# Arduino_nano.net
KiCad netlist of a schematic drawn in Altium Designer
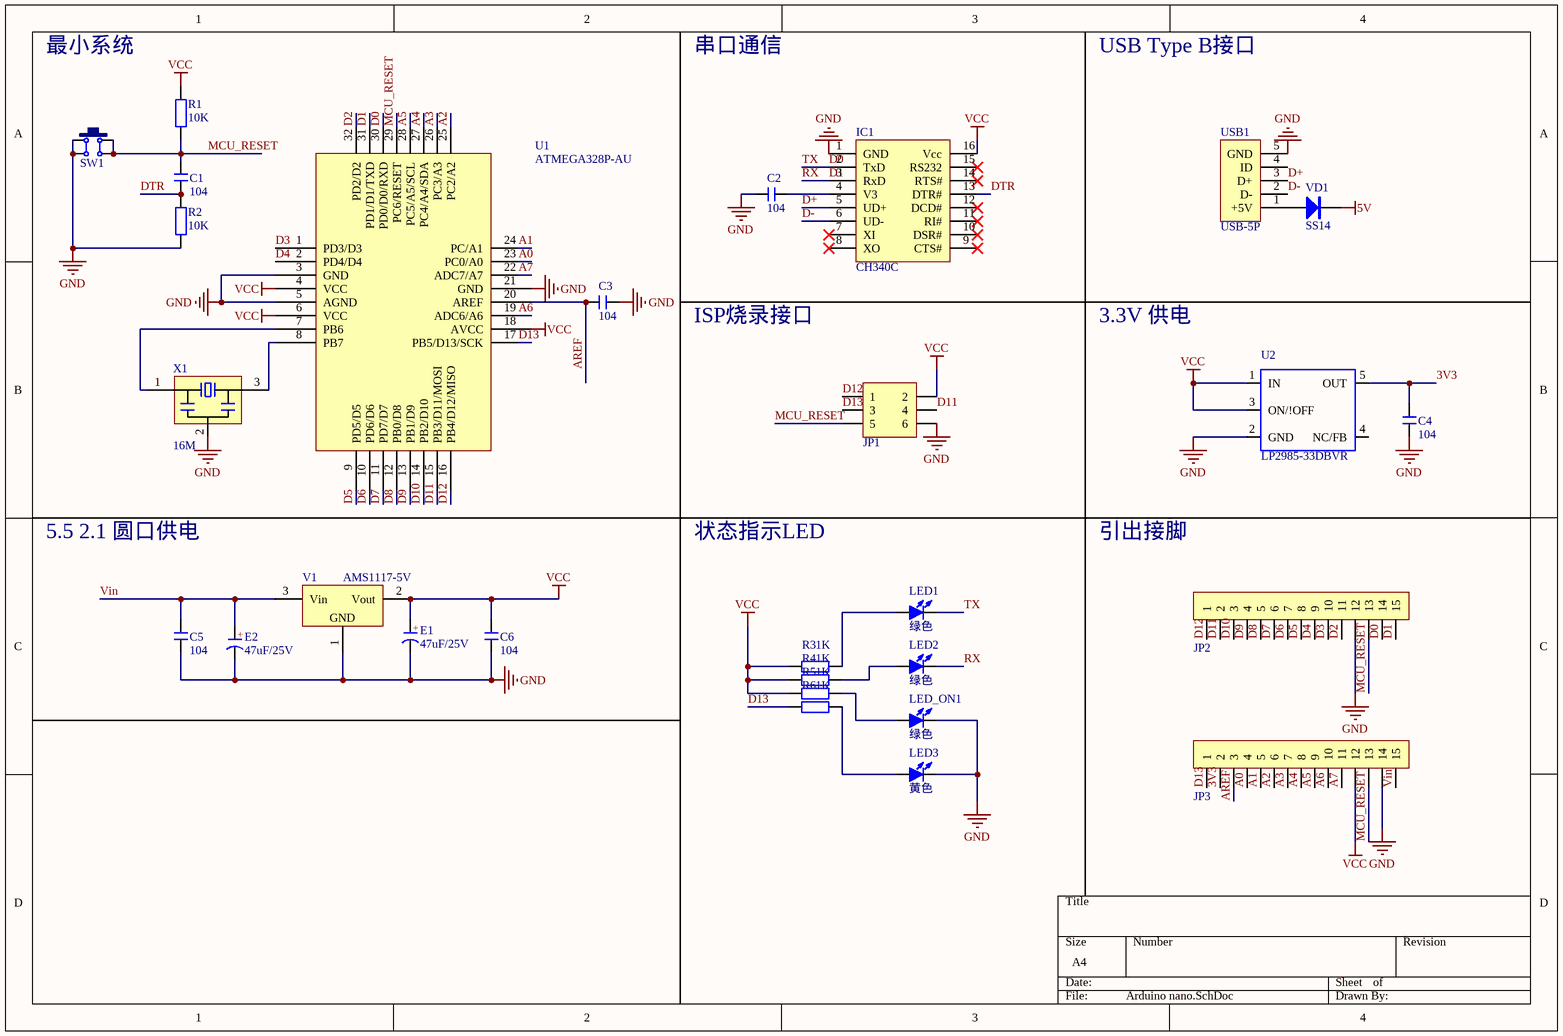
[diagram p0: Arduino nano.SchDoc]

(export (version "E")
  (design (tool "Eeschema 10.0.6"))
  (components
    (comp (ref "C1")
      (value "104")
      (footprint "C 0603_L")
      (description "无极性贴片电容")
      (fields (field (name "版权归属") "源创客"))
      (libsource (lib "电阻-电容-电感") (part "C"))
    )
    (comp (ref "C2")
      (value "104")
      (footprint "C 0603_L")
      (description "无极性贴片电容")
      (fields (field (name "版权归属") "源创客"))
      (libsource (lib "电阻-电容-电感") (part "C"))
    )
    (comp (ref "C3")
      (value "104")
      (footprint "C 0603_L")
      (description "无极性贴片电容")
      (fields (field (name "版权归属") "源创客"))
      (libsource (lib "电阻-电容-电感") (part "C"))
    )
    (comp (ref "C4")
      (value "104")
      (footprint "C 0603_L")
      (description "无极性贴片电容")
      (fields (field (name "版权归属") "源创客"))
      (libsource (lib "电阻-电容-电感") (part "C"))
    )
    (comp (ref "C5")
      (value "104")
      (footprint "C 0603_L")
      (description "无极性贴片电容")
      (fields (field (name "版权归属") "源创客"))
      (libsource (lib "电阻-电容-电感") (part "C"))
    )
    (comp (ref "C6")
      (value "104")
      (footprint "C 0603_L")
      (description "无极性贴片电容")
      (fields (field (name "版权归属") "源创客"))
      (libsource (lib "电阻-电容-电感") (part "C"))
    )
    (comp (ref "E1")
      (value "47uF/25V")
      (footprint "CD A(3216)")
      (description "贴片电解电容")
      (fields (field (name "版权归属") "源创客"))
      (libsource (lib "电阻-电容-电感") (part "C-CM"))
    )
    (comp (ref "E2")
      (value "47uF/25V")
      (footprint "CD A(3216)")
      (description "贴片电解电容")
      (fields (field (name "版权归属") "源创客"))
      (libsource (lib "电阻-电容-电感") (part "C-CM"))
    )
    (comp (ref "IC1")
      (value "CH340C")
      (footprint "SOP16_L")
      (description "串口转USB")
      (fields (field (name "版权归属") "源创客"))
      (libsource (lib "IC芯片") (part "CH340G"))
    )
    (comp (ref "JP1")
      (value "Header3X2")
      (footprint "HDR2.54-LI-2x3P")
      (description "3*2P接插件")
      (fields (field (name "版权归属") "源创客"))
      (libsource (lib "接插件") (part "Header 3X2"))
    )
    (comp (ref "JP2")
      (value "HDR-1X15")
      (footprint "HDR2.54-LI-15P")
      (description "15P接插件")
      (fields (field (name "版权归属") "源创客"))
      (libsource (lib "4.6   - 接插件-脚距2.54") (part "Header 15"))
    )
    (comp (ref "JP3")
      (value "HDR-1X15")
      (footprint "HDR2.54-LI-15P")
      (description "15P接插件")
      (fields (field (name "版权归属") "源创客"))
      (libsource (lib "4.6   - 接插件-脚距2.54") (part "Header 15"))
    )
    (comp (ref "LED1")
      (value "绿色")
      (footprint "LED 0603B")
      (description "贴片LED")
      (fields (field (name "版权归属") "源创客"))
      (libsource (lib "LED") (part "LED-SMD"))
    )
    (comp (ref "LED2")
      (value "绿色")
      (footprint "LED 0603B")
      (description "贴片LED")
      (fields (field (name "版权归属") "源创客"))
      (libsource (lib "LED") (part "LED-SMD"))
    )
    (comp (ref "LED3")
      (value "黄色")
      (footprint "LED 0603B")
      (description "贴片LED")
      (fields (field (name "版权归属") "源创客"))
      (libsource (lib "LED") (part "LED-SMD"))
    )
    (comp (ref "LED_ON1")
      (value "绿色")
      (footprint "LED 0603B")
      (description "贴片LED")
      (fields (field (name "版权归属") "源创客"))
      (libsource (lib "LED") (part "LED-SMD"))
    )
    (comp (ref "R1")
      (value "10K")
      (footprint "R 0603_L")
      (description "贴片电阻")
      (fields (field (name "版权归属") "源创客"))
      (libsource (lib "电阻-电容-电感") (part "R"))
    )
    (comp (ref "R2")
      (value "10K")
      (footprint "R 0603_L")
      (description "贴片电阻")
      (fields (field (name "版权归属") "源创客"))
      (libsource (lib "电阻-电容-电感") (part "R"))
    )
    (comp (ref "R3")
      (value "1K")
      (footprint "R 0603_L")
      (description "贴片电阻")
      (fields (field (name "版权归属") "源创客"))
      (libsource (lib "电阻-电容-电感") (part "R"))
    )
    (comp (ref "R4")
      (value "1K")
      (footprint "R 0603_L")
      (description "贴片电阻")
      (fields (field (name "版权归属") "源创客"))
      (libsource (lib "电阻-电容-电感") (part "R"))
    )
    (comp (ref "R5")
      (value "1K")
      (footprint "R 0603_L")
      (description "贴片电阻")
      (fields (field (name "版权归属") "源创客"))
      (libsource (lib "电阻-电容-电感") (part "R"))
    )
    (comp (ref "R6")
      (value "1K")
      (footprint "R 0603_L")
      (description "贴片电阻")
      (fields (field (name "版权归属") "源创客"))
      (libsource (lib "电阻-电容-电感") (part "R"))
    )
    (comp (ref "SW1")
      (value "4x4x1.5")
      (footprint "TS4x4x1.5")
      (description "防水轻触开关")
      (fields (field (name "版权归属") "源创客"))
      (libsource (lib "5.1   - 按键-开关") (part "TS-030"))
    )
    (comp (ref "U1")
      (value "ATMEGA328P-AU")
      (footprint "LQFP32 7X7_L")
      (description "AVR单片机")
      (fields (field (name "版权归属") "源创客"))
      (libsource (lib "Atmel系列单片机") (part "ATMEGA328P"))
    )
    (comp (ref "U2")
      (value "LP2985-33DBVR")
      (footprint "SOT23-5L")
      (libsource (lib "*") (part "LP2985-XXDBVR33"))
    )
    (comp (ref "USB1")
      (value "USB-5P")
      (footprint "USB-MICRO_A")
      (description "微型USB母座")
      (fields (field (name "版权归属") "源创客"))
      (libsource (lib "4.1   - 接口类") (part "USB-5P"))
    )
    (comp (ref "V1")
      (value "AMS1117-5V")
      (footprint "SOT223_N")
      (description "三端稳压芯片")
      (fields (field (name "版权归属") "源创客"))
      (libsource (lib "IC芯片") (part "AMS1117"))
    )
    (comp (ref "VD1")
      (value "SS14")
      (footprint "SMA")
      (description "肖特基二极管")
      (fields (field (name "版权归属") "源创客"))
      (libsource (lib "二极管-整流桥") (part "SS14"))
    )
    (comp (ref "X1")
      (value "16M")
      (footprint "OSC-3.2-1.3-3P")
      (description "3脚晶振")
      (fields (field (name "版权归属") "源创客"))
      (libsource (lib "保险丝-晶振") (part "XTAL-3"))
    )
  )
  (nets
    (net (code "1") (name "/3V3") (class "Default")
      (node (ref "C4") (pin "2") (pinfunction "2_2") (pintype "passive"))
      (node (ref "JP3") (pin "2") (pinfunction "2_2") (pintype "passive"))
      (node (ref "U2") (pin "5") (pinfunction "OUT_5") (pintype "passive"))
    )
    (net (code "2") (name "/A0") (class "Default")
      (node (ref "JP3") (pin "4") (pinfunction "4_4") (pintype "passive"))
      (node (ref "U1") (pin "23") (pinfunction "PC0/A0_23") (pintype "passive"))
    )
    (net (code "3") (name "/A1") (class "Default")
      (node (ref "JP3") (pin "5") (pinfunction "5_5") (pintype "passive"))
      (node (ref "U1") (pin "24") (pinfunction "PC/A1_24") (pintype "passive"))
    )
    (net (code "4") (name "/A2") (class "Default")
      (node (ref "JP3") (pin "6") (pinfunction "6_6") (pintype "passive"))
      (node (ref "U1") (pin "25") (pinfunction "PC2/A2_25") (pintype "passive"))
    )
    (net (code "5") (name "/A3") (class "Default")
      (node (ref "JP3") (pin "7") (pinfunction "7_7") (pintype "passive"))
      (node (ref "U1") (pin "26") (pinfunction "PC3/A3_26") (pintype "passive"))
    )
    (net (code "6") (name "/A4") (class "Default")
      (node (ref "JP3") (pin "8") (pinfunction "8_8") (pintype "passive"))
      (node (ref "U1") (pin "27") (pinfunction "PC4/A4/SDA_27") (pintype "passive"))
    )
    (net (code "7") (name "/A5") (class "Default")
      (node (ref "JP3") (pin "9") (pinfunction "9_9") (pintype "passive"))
      (node (ref "U1") (pin "28") (pinfunction "PC5/A5/SCL_28") (pintype "passive"))
    )
    (net (code "8") (name "/A6") (class "Default")
      (node (ref "JP3") (pin "10") (pinfunction "10_10") (pintype "passive"))
      (node (ref "U1") (pin "19") (pinfunction "ADC6/A6_19") (pintype "passive"))
    )
    (net (code "9") (name "/A7") (class "Default")
      (node (ref "JP3") (pin "11") (pinfunction "11_11") (pintype "passive"))
      (node (ref "U1") (pin "22") (pinfunction "ADC7/A7_22") (pintype "passive"))
    )
    (net (code "10") (name "/AREF") (class "Default")
      (node (ref "C3") (pin "1") (pinfunction "1_1") (pintype "passive"))
      (node (ref "JP3") (pin "3") (pinfunction "3_3") (pintype "passive"))
      (node (ref "U1") (pin "20") (pinfunction "AREF_20") (pintype "passive"))
    )
    (net (code "11") (name "/D+") (class "Default")
      (node (ref "IC1") (pin "5") (pinfunction "UD+_5") (pintype "passive"))
      (node (ref "USB1") (pin "3") (pinfunction "D+_3") (pintype "passive"))
    )
    (net (code "12") (name "/D-") (class "Default")
      (node (ref "IC1") (pin "6") (pinfunction "UD-_6") (pintype "passive"))
      (node (ref "USB1") (pin "2") (pinfunction "D-_2") (pintype "passive"))
    )
    (net (code "13") (name "/D0") (class "Default")
      (node (ref "IC1") (pin "2") (pinfunction "TxD_2") (pintype "passive"))
      (node (ref "JP2") (pin "14") (pinfunction "14_14") (pintype "passive"))
      (node (ref "LED1") (pin "2") (pinfunction "K_2") (pintype "passive"))
      (node (ref "U1") (pin "30") (pinfunction "PD0/D0/RXD_30") (pintype "passive"))
    )
    (net (code "14") (name "/D1") (class "Default")
      (node (ref "IC1") (pin "3") (pinfunction "RxD_3") (pintype "passive"))
      (node (ref "JP2") (pin "15") (pinfunction "15_15") (pintype "passive"))
      (node (ref "LED2") (pin "2") (pinfunction "K_2") (pintype "passive"))
      (node (ref "U1") (pin "31") (pinfunction "PD1/D1/TXD_31") (pintype "passive"))
    )
    (net (code "15") (name "/D2") (class "Default")
      (node (ref "JP2") (pin "11") (pinfunction "11_11") (pintype "passive"))
      (node (ref "U1") (pin "32") (pinfunction "PD2/D2_32") (pintype "passive"))
    )
    (net (code "16") (name "/D3") (class "Default")
      (node (ref "JP2") (pin "10") (pinfunction "10_10") (pintype "passive"))
      (node (ref "U1") (pin "1") (pinfunction "PD3/D3_1") (pintype "passive"))
    )
    (net (code "17") (name "/D4") (class "Default")
      (node (ref "JP2") (pin "9") (pinfunction "9_9") (pintype "passive"))
      (node (ref "U1") (pin "2") (pinfunction "PD4/D4_2") (pintype "passive"))
    )
    (net (code "18") (name "/D5") (class "Default")
      (node (ref "JP2") (pin "8") (pinfunction "8_8") (pintype "passive"))
      (node (ref "U1") (pin "9") (pinfunction "PD5/D5_9") (pintype "passive"))
    )
    (net (code "19") (name "/D6") (class "Default")
      (node (ref "JP2") (pin "7") (pinfunction "7_7") (pintype "passive"))
      (node (ref "U1") (pin "10") (pinfunction "PD6/D6_10") (pintype "passive"))
    )
    (net (code "20") (name "/D7") (class "Default")
      (node (ref "JP2") (pin "6") (pinfunction "6_6") (pintype "passive"))
      (node (ref "U1") (pin "11") (pinfunction "PD7/D7_11") (pintype "passive"))
    )
    (net (code "21") (name "/D8") (class "Default")
      (node (ref "JP2") (pin "5") (pinfunction "5_5") (pintype "passive"))
      (node (ref "U1") (pin "12") (pinfunction "PB0/D8_12") (pintype "passive"))
    )
    (net (code "22") (name "/D9") (class "Default")
      (node (ref "JP2") (pin "4") (pinfunction "4_4") (pintype "passive"))
      (node (ref "U1") (pin "13") (pinfunction "PB1/D9_13") (pintype "passive"))
    )
    (net (code "23") (name "/D10") (class "Default")
      (node (ref "JP2") (pin "3") (pinfunction "3_3") (pintype "passive"))
      (node (ref "U1") (pin "14") (pinfunction "PB2/D10_14") (pintype "passive"))
    )
    (net (code "24") (name "/D11") (class "Default")
      (node (ref "JP1") (pin "4") (pinfunction "4_4") (pintype "passive"))
      (node (ref "JP2") (pin "2") (pinfunction "2_2") (pintype "passive"))
      (node (ref "U1") (pin "15") (pinfunction "PB3/D11/MOSI_15") (pintype "passive"))
    )
    (net (code "25") (name "/D12") (class "Default")
      (node (ref "JP1") (pin "1") (pinfunction "1_1") (pintype "passive"))
      (node (ref "JP2") (pin "1") (pinfunction "1_1") (pintype "passive"))
      (node (ref "U1") (pin "16") (pinfunction "PB4/D12/MISO_16") (pintype "passive"))
    )
    (net (code "26") (name "/D13") (class "Default")
      (node (ref "JP1") (pin "3") (pinfunction "3_3") (pintype "passive"))
      (node (ref "JP3") (pin "1") (pinfunction "1_1") (pintype "passive"))
      (node (ref "R6") (pin "2") (pinfunction "2_2") (pintype "passive"))
      (node (ref "U1") (pin "17") (pinfunction "PB5/D13/SCK_17") (pintype "passive"))
    )
    (net (code "27") (name "/DTR") (class "Default")
      (node (ref "C1") (pin "1") (pinfunction "1_1") (pintype "passive"))
      (node (ref "IC1") (pin "13") (pinfunction "DTR#_13") (pintype "passive"))
      (node (ref "R2") (pin "2") (pinfunction "2_2") (pintype "passive"))
    )
    (net (code "28") (name "/MCU_RESET") (class "Default")
      (node (ref "C1") (pin "2") (pinfunction "2_2") (pintype "passive"))
      (node (ref "JP1") (pin "5") (pinfunction "5_5") (pintype "passive"))
      (node (ref "JP2") (pin "13") (pinfunction "13_13") (pintype "passive"))
      (node (ref "JP3") (pin "13") (pinfunction "13_13") (pintype "passive"))
      (node (ref "R1") (pin "2") (pinfunction "2_2") (pintype "passive"))
      (node (ref "SW1") (pin "2") (pinfunction "2_2") (pintype "passive"))
      (node (ref "SW1") (pin "3") (pinfunction "3_3") (pintype "passive"))
      (node (ref "U1") (pin "29") (pinfunction "PC6/RESET_29") (pintype "passive"))
    )
    (net (code "29") (name "/Vin") (class "Default")
      (node (ref "C5") (pin "2") (pinfunction "2_2") (pintype "passive"))
      (node (ref "E2") (pin "1") (pinfunction "A_1") (pintype "passive"))
      (node (ref "JP3") (pin "15") (pinfunction "15_15") (pintype "passive"))
      (node (ref "V1") (pin "3") (pinfunction "Vin_3") (pintype "passive"))
    )
    (net (code "30") (name "5V") (class "Default")
      (node (ref "VD1") (pin "2") (pinfunction "K_2") (pintype "passive"))
    )
    (net (code "31") (name "GND") (class "Default")
      (node (ref "C2") (pin "1") (pinfunction "1_1") (pintype "passive"))
      (node (ref "C3") (pin "2") (pinfunction "2_2") (pintype "passive"))
      (node (ref "C4") (pin "1") (pinfunction "1_1") (pintype "passive"))
      (node (ref "C5") (pin "1") (pinfunction "1_1") (pintype "passive"))
      (node (ref "C6") (pin "1") (pinfunction "1_1") (pintype "passive"))
      (node (ref "E1") (pin "2") (pinfunction "K_2") (pintype "passive"))
      (node (ref "E2") (pin "2") (pinfunction "K_2") (pintype "passive"))
      (node (ref "IC1") (pin "1") (pinfunction "GND_1") (pintype "passive"))
      (node (ref "JP1") (pin "6") (pinfunction "6_6") (pintype "passive"))
      (node (ref "JP2") (pin "12") (pinfunction "12_12") (pintype "passive"))
      (node (ref "JP3") (pin "14") (pinfunction "14_14") (pintype "passive"))
      (node (ref "LED3") (pin "2") (pinfunction "K_2") (pintype "passive"))
      (node (ref "LED_ON1") (pin "2") (pinfunction "K_2") (pintype "passive"))
      (node (ref "R2") (pin "1") (pinfunction "1_1") (pintype "passive"))
      (node (ref "SW1") (pin "1") (pinfunction "1_1") (pintype "passive"))
      (node (ref "SW1") (pin "4") (pinfunction "4_4") (pintype "passive"))
      (node (ref "U1") (pin "21") (pinfunction "GND_21") (pintype "passive"))
      (node (ref "U1") (pin "3") (pinfunction "GND_3") (pintype "passive"))
      (node (ref "U1") (pin "5") (pinfunction "AGND_5") (pintype "passive"))
      (node (ref "U2") (pin "2") (pinfunction "GND_2") (pintype "passive"))
      (node (ref "USB1") (pin "5") (pinfunction "GND_5") (pintype "passive"))
      (node (ref "V1") (pin "1") (pinfunction "GND_1") (pintype "passive"))
      (node (ref "X1") (pin "2") (pinfunction "2_2") (pintype "passive"))
    )
    (net (code "32") (name "Net-(IC1-V3)") (class "Default")
      (node (ref "C2") (pin "2") (pinfunction "2_2") (pintype "passive"))
      (node (ref "IC1") (pin "4") (pinfunction "V3_4") (pintype "passive"))
    )
    (net (code "33") (name "Net-(LED1-A)") (class "Default")
      (node (ref "LED1") (pin "1") (pinfunction "A_1") (pintype "passive"))
      (node (ref "R3") (pin "1") (pinfunction "1_1") (pintype "passive"))
    )
    (net (code "34") (name "Net-(LED2-A)") (class "Default")
      (node (ref "LED2") (pin "1") (pinfunction "A_1") (pintype "passive"))
      (node (ref "R4") (pin "1") (pinfunction "1_1") (pintype "passive"))
    )
    (net (code "35") (name "Net-(LED3-A)") (class "Default")
      (node (ref "LED3") (pin "1") (pinfunction "A_1") (pintype "passive"))
      (node (ref "R6") (pin "1") (pinfunction "1_1") (pintype "passive"))
    )
    (net (code "36") (name "Net-(LED_ON1-A)") (class "Default")
      (node (ref "LED_ON1") (pin "1") (pinfunction "A_1") (pintype "passive"))
      (node (ref "R5") (pin "1") (pinfunction "1_1") (pintype "passive"))
    )
    (net (code "37") (name "Net-(U1-PB6)") (class "Default")
      (node (ref "U1") (pin "7") (pinfunction "PB6_7") (pintype "passive"))
      (node (ref "X1") (pin "1") (pinfunction "1_1") (pintype "passive"))
    )
    (net (code "38") (name "Net-(U1-PB7)") (class "Default")
      (node (ref "U1") (pin "8") (pinfunction "PB7_8") (pintype "passive"))
      (node (ref "X1") (pin "3") (pinfunction "3_3") (pintype "passive"))
    )
    (net (code "39") (name "Net-(USB1-+5V)") (class "Default")
      (node (ref "USB1") (pin "1") (pinfunction "+5V_1") (pintype "passive"))
      (node (ref "VD1") (pin "1") (pinfunction "A_1") (pintype "passive"))
    )
    (net (code "40") (name "VCC") (class "Default")
      (node (ref "C6") (pin "2") (pinfunction "2_2") (pintype "passive"))
      (node (ref "E1") (pin "1") (pinfunction "A_1") (pintype "passive"))
      (node (ref "IC1") (pin "16") (pinfunction "Vcc_16") (pintype "passive"))
      (node (ref "JP1") (pin "2") (pinfunction "2_2") (pintype "passive"))
      (node (ref "JP3") (pin "12") (pinfunction "12_12") (pintype "passive"))
      (node (ref "R1") (pin "1") (pinfunction "1_1") (pintype "passive"))
      (node (ref "R3") (pin "2") (pinfunction "2_2") (pintype "passive"))
      (node (ref "R4") (pin "2") (pinfunction "2_2") (pintype "passive"))
      (node (ref "R5") (pin "2") (pinfunction "2_2") (pintype "passive"))
      (node (ref "U1") (pin "18") (pinfunction "AVCC_18") (pintype "passive"))
      (node (ref "U1") (pin "4") (pinfunction "VCC_4") (pintype "passive"))
      (node (ref "U1") (pin "6") (pinfunction "VCC_6") (pintype "passive"))
      (node (ref "U2") (pin "1") (pinfunction "IN_1") (pintype "passive"))
      (node (ref "U2") (pin "3") (pinfunction "ON/!OFF_3") (pintype "passive"))
      (node (ref "V1") (pin "2") (pinfunction "Vout_2") (pintype "passive"))
    )
    (net (code "41") (name "unconnected-(IC1-CTS#-Pad9)") (class "Default")
      (node (ref "IC1") (pin "9") (pinfunction "CTS#_9") (pintype "passive+no_connect"))
    )
    (net (code "42") (name "unconnected-(IC1-DCD#-Pad12)") (class "Default")
      (node (ref "IC1") (pin "12") (pinfunction "DCD#_12") (pintype "passive+no_connect"))
    )
    (net (code "43") (name "unconnected-(IC1-DSR#-Pad10)") (class "Default")
      (node (ref "IC1") (pin "10") (pinfunction "DSR#_10") (pintype "passive+no_connect"))
    )
    (net (code "44") (name "unconnected-(IC1-RI#-Pad11)") (class "Default")
      (node (ref "IC1") (pin "11") (pinfunction "RI#_11") (pintype "passive+no_connect"))
    )
    (net (code "45") (name "unconnected-(IC1-RS232-Pad15)") (class "Default")
      (node (ref "IC1") (pin "15") (pinfunction "RS232_15") (pintype "passive+no_connect"))
    )
    (net (code "46") (name "unconnected-(IC1-RTS#-Pad14)") (class "Default")
      (node (ref "IC1") (pin "14") (pinfunction "RTS#_14") (pintype "passive+no_connect"))
    )
    (net (code "47") (name "unconnected-(IC1-XI-Pad7)") (class "Default")
      (node (ref "IC1") (pin "7") (pinfunction "XI_7") (pintype "passive+no_connect"))
    )
    (net (code "48") (name "unconnected-(IC1-XO-Pad8)") (class "Default")
      (node (ref "IC1") (pin "8") (pinfunction "XO_8") (pintype "passive+no_connect"))
    )
    (net (code "49") (name "unconnected-(U2-NC{slash}FB-Pad4)") (class "Default")
      (node (ref "U2") (pin "4") (pinfunction "NC/FB_4") (pintype "passive"))
    )
    (net (code "50") (name "unconnected-(USB1-ID-Pad4)") (class "Default")
      (node (ref "USB1") (pin "4") (pinfunction "ID_4") (pintype "passive"))
    )
  )
)
